# schematic.net
KiCad netlist of a schematic drawn in EasyEDA
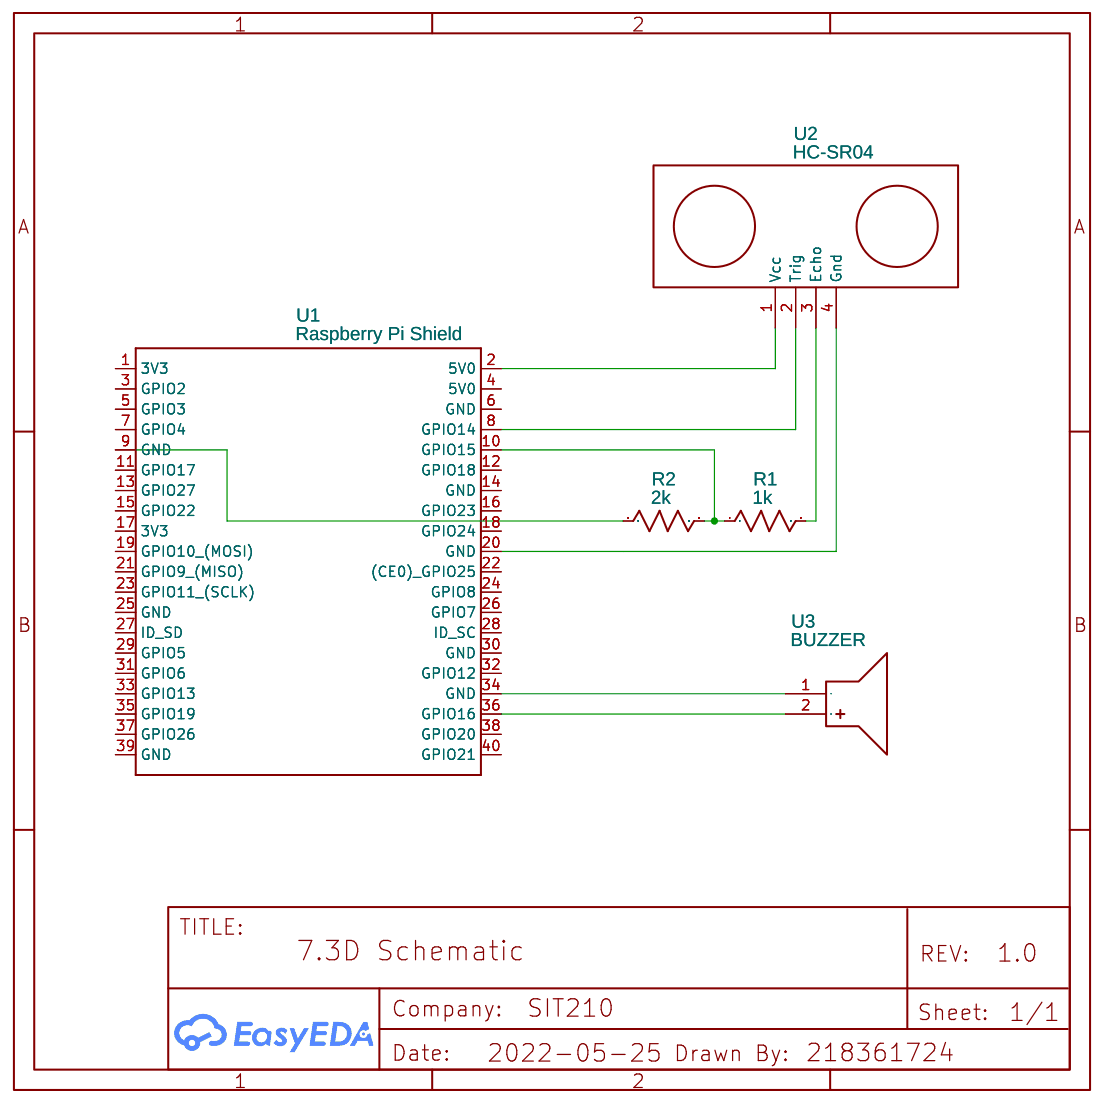
[diagram p0: schematic sheet]

(export (version "E")
  (design (tool "Eeschema 10.0.6"))
  (components
    (comp (ref "R1") (value "1k") (libsource (lib "") (part "R_0603_US")))
    (comp (ref "R2") (value "2k") (libsource (lib "") (part "R_0603_US")))
    (comp (ref "U1")
      (value "Raspberry Pi Shield")
      (fields (field (name "BOM_Manufacturer Part") "RaspberryPi 3"))
      (libsource (lib "") (part "RaspberryPi 3 Hat"))
    )
    (comp (ref "U2") (value "HC-SR04") (libsource (lib "") (part "HC-SR04 COPY")))
    (comp (ref "U3")
      (value "BUZZER")
      (fields
        (field (name "BOM_Manufacturer Part") "buzzer")
        (field (name "BOM_Supplier Part") "C9900014030")
      )
      (libsource (lib "") (part "BUZZER"))
    )
  )
  (nets
    (net (code "1") (name "Net-(R2-Pad1)") (class "Default")
      (node (ref "R2") (pin "1") (pinfunction "1_1") (pintype "unspecified"))
      (node (ref "U1") (pin "9") (pinfunction "GND_9") (pintype "unspecified"))
    )
    (net (code "2") (name "Net-(U1-GPIO14)") (class "Default")
      (node (ref "U1") (pin "8") (pinfunction "GPIO14_8") (pintype "unspecified"))
      (node (ref "U2") (pin "2") (pinfunction "Trig_2") (pintype "unspecified"))
    )
    (net (code "3") (name "Net-(U1-GPIO15)") (class "Default")
      (node (ref "R1") (pin "1") (pinfunction "1_1") (pintype "unspecified"))
      (node (ref "R2") (pin "2") (pinfunction "2_2") (pintype "unspecified"))
      (node (ref "U1") (pin "10") (pinfunction "GPIO15_10") (pintype "unspecified"))
    )
    (net (code "4") (name "Net-(U1-GPIO16)") (class "Default")
      (node (ref "U1") (pin "36") (pinfunction "GPIO16_36") (pintype "unspecified"))
      (node (ref "U3") (pin "2") (pinfunction "+_2") (pintype "unspecified"))
    )
    (net (code "5") (name "Net-(U2-Echo)") (class "Default")
      (node (ref "R1") (pin "2") (pinfunction "2_2") (pintype "unspecified"))
      (node (ref "U2") (pin "3") (pinfunction "Echo_3") (pintype "unspecified"))
    )
    (net (code "6") (name "Net-(U2-Gnd)") (class "Default")
      (node (ref "U1") (pin "20") (pinfunction "GND_20") (pintype "unspecified"))
      (node (ref "U2") (pin "4") (pinfunction "Gnd_4") (pintype "unspecified"))
    )
    (net (code "7") (name "Net-(U2-Vcc)") (class "Default")
      (node (ref "U1") (pin "2") (pinfunction "5V0_2") (pintype "unspecified"))
      (node (ref "U2") (pin "1") (pinfunction "Vcc_1") (pintype "unspecified"))
    )
    (net (code "8") (name "Net-(U3--)") (class "Default")
      (node (ref "U1") (pin "34") (pinfunction "GND_34") (pintype "unspecified"))
      (node (ref "U3") (pin "1") (pinfunction "-_1") (pintype "unspecified"))
    )
    (net (code "9") (name "unconnected-(U1-(CE0)_GPIO25-Pad22)") (class "Default")
      (node (ref "U1") (pin "22") (pinfunction "(CE0)_GPIO25_22") (pintype "unspecified"))
    )
    (net (code "10") (name "unconnected-(U1-3V3-Pad1)") (class "Default")
      (node (ref "U1") (pin "1") (pinfunction "3V3_1") (pintype "unspecified"))
    )
    (net (code "11") (name "unconnected-(U1-3V3-Pad17)") (class "Default")
      (node (ref "U1") (pin "17") (pinfunction "3V3_17") (pintype "unspecified"))
    )
    (net (code "12") (name "unconnected-(U1-5V0-Pad4)") (class "Default")
      (node (ref "U1") (pin "4") (pinfunction "5V0_4") (pintype "unspecified"))
    )
    (net (code "13") (name "unconnected-(U1-GND-Pad6)") (class "Default")
      (node (ref "U1") (pin "6") (pinfunction "GND_6") (pintype "unspecified"))
    )
    (net (code "14") (name "unconnected-(U1-GND-Pad14)") (class "Default")
      (node (ref "U1") (pin "14") (pinfunction "GND_14") (pintype "unspecified"))
    )
    (net (code "15") (name "unconnected-(U1-GND-Pad25)") (class "Default")
      (node (ref "U1") (pin "25") (pinfunction "GND_25") (pintype "unspecified"))
    )
    (net (code "16") (name "unconnected-(U1-GND-Pad30)") (class "Default")
      (node (ref "U1") (pin "30") (pinfunction "GND_30") (pintype "unspecified"))
    )
    (net (code "17") (name "unconnected-(U1-GND-Pad39)") (class "Default")
      (node (ref "U1") (pin "39") (pinfunction "GND_39") (pintype "unspecified"))
    )
    (net (code "18") (name "unconnected-(U1-GPIO2-Pad3)") (class "Default")
      (node (ref "U1") (pin "3") (pinfunction "GPIO2_3") (pintype "unspecified"))
    )
    (net (code "19") (name "unconnected-(U1-GPIO3-Pad5)") (class "Default")
      (node (ref "U1") (pin "5") (pinfunction "GPIO3_5") (pintype "unspecified"))
    )
    (net (code "20") (name "unconnected-(U1-GPIO4-Pad7)") (class "Default")
      (node (ref "U1") (pin "7") (pinfunction "GPIO4_7") (pintype "unspecified"))
    )
    (net (code "21") (name "unconnected-(U1-GPIO5-Pad29)") (class "Default")
      (node (ref "U1") (pin "29") (pinfunction "GPIO5_29") (pintype "unspecified"))
    )
    (net (code "22") (name "unconnected-(U1-GPIO6-Pad31)") (class "Default")
      (node (ref "U1") (pin "31") (pinfunction "GPIO6_31") (pintype "unspecified"))
    )
    (net (code "23") (name "unconnected-(U1-GPIO7-Pad26)") (class "Default")
      (node (ref "U1") (pin "26") (pinfunction "GPIO7_26") (pintype "unspecified"))
    )
    (net (code "24") (name "unconnected-(U1-GPIO8-Pad24)") (class "Default")
      (node (ref "U1") (pin "24") (pinfunction "GPIO8_24") (pintype "unspecified"))
    )
    (net (code "25") (name "unconnected-(U1-GPIO9_(MISO)-Pad21)") (class "Default")
      (node (ref "U1") (pin "21") (pinfunction "GPIO9_(MISO)_21") (pintype "unspecified"))
    )
    (net (code "26") (name "unconnected-(U1-GPIO10_(MOSI)-Pad19)") (class "Default")
      (node (ref "U1") (pin "19") (pinfunction "GPIO10_(MOSI)_19") (pintype "unspecified"))
    )
    (net (code "27") (name "unconnected-(U1-GPIO11_(SCLK)-Pad23)") (class "Default")
      (node (ref "U1") (pin "23") (pinfunction "GPIO11_(SCLK)_23") (pintype "unspecified"))
    )
    (net (code "28") (name "unconnected-(U1-GPIO12-Pad32)") (class "Default")
      (node (ref "U1") (pin "32") (pinfunction "GPIO12_32") (pintype "unspecified"))
    )
    (net (code "29") (name "unconnected-(U1-GPIO13-Pad33)") (class "Default")
      (node (ref "U1") (pin "33") (pinfunction "GPIO13_33") (pintype "unspecified"))
    )
    (net (code "30") (name "unconnected-(U1-GPIO17-Pad11)") (class "Default")
      (node (ref "U1") (pin "11") (pinfunction "GPIO17_11") (pintype "unspecified"))
    )
    (net (code "31") (name "unconnected-(U1-GPIO18-Pad12)") (class "Default")
      (node (ref "U1") (pin "12") (pinfunction "GPIO18_12") (pintype "unspecified"))
    )
    (net (code "32") (name "unconnected-(U1-GPIO19-Pad35)") (class "Default")
      (node (ref "U1") (pin "35") (pinfunction "GPIO19_35") (pintype "unspecified"))
    )
    (net (code "33") (name "unconnected-(U1-GPIO20-Pad38)") (class "Default")
      (node (ref "U1") (pin "38") (pinfunction "GPIO20_38") (pintype "unspecified"))
    )
    (net (code "34") (name "unconnected-(U1-GPIO21-Pad40)") (class "Default")
      (node (ref "U1") (pin "40") (pinfunction "GPIO21_40") (pintype "unspecified"))
    )
    (net (code "35") (name "unconnected-(U1-GPIO22-Pad15)") (class "Default")
      (node (ref "U1") (pin "15") (pinfunction "GPIO22_15") (pintype "unspecified"))
    )
    (net (code "36") (name "unconnected-(U1-GPIO23-Pad16)") (class "Default")
      (node (ref "U1") (pin "16") (pinfunction "GPIO23_16") (pintype "unspecified"))
    )
    (net (code "37") (name "unconnected-(U1-GPIO24-Pad18)") (class "Default")
      (node (ref "U1") (pin "18") (pinfunction "GPIO24_18") (pintype "unspecified"))
    )
    (net (code "38") (name "unconnected-(U1-GPIO26-Pad37)") (class "Default")
      (node (ref "U1") (pin "37") (pinfunction "GPIO26_37") (pintype "unspecified"))
    )
    (net (code "39") (name "unconnected-(U1-GPIO27-Pad13)") (class "Default")
      (node (ref "U1") (pin "13") (pinfunction "GPIO27_13") (pintype "unspecified"))
    )
    (net (code "40") (name "unconnected-(U1-ID_SC-Pad28)") (class "Default")
      (node (ref "U1") (pin "28") (pinfunction "ID_SC_28") (pintype "unspecified"))
    )
    (net (code "41") (name "unconnected-(U1-ID_SD-Pad27)") (class "Default")
      (node (ref "U1") (pin "27") (pinfunction "ID_SD_27") (pintype "unspecified"))
    )
  )
)
